# gydrodrive_discreteControl.net
KiCad netlist of a schematic drawn in Altium Designer
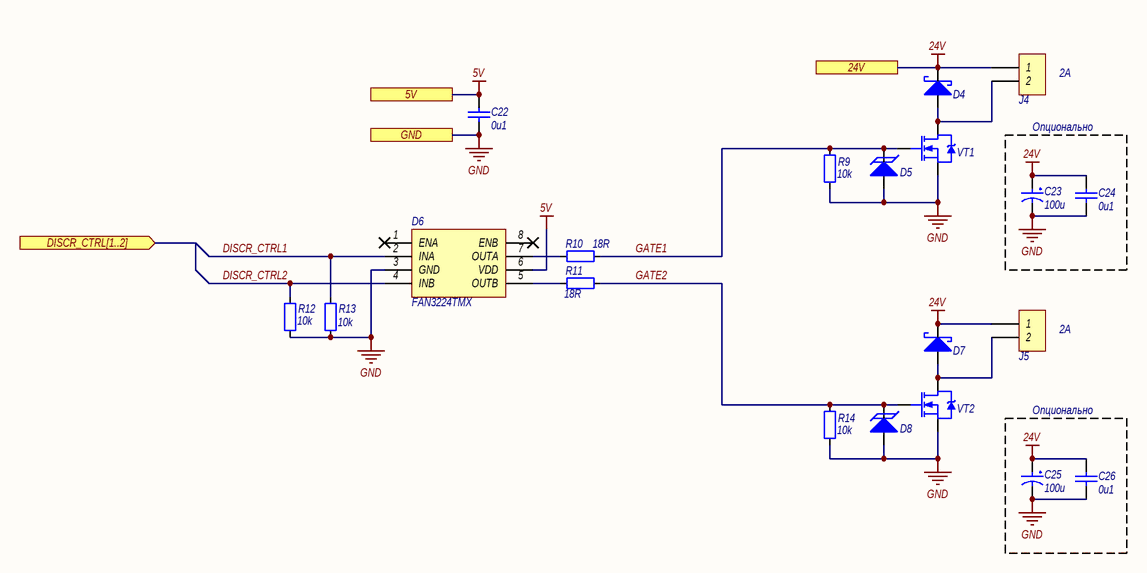
[diagram p0: gydrodrive_discreteControl.SchDoc]

(export (version "E")
  (design (tool "Eeschema 10.0.6"))
  (components
    (comp (ref "C22")
      (value "CAP_0805")
      (footprint "CAPC2012-0805M")
      (description "Конденсатор керамический, корпус 0805")
      (fields
        (field (name "CAPACITANCE") "0u1")
        (field (name "PART NUMBER") "CAPC_0805")
        (field (name "VOLTAGE") "50V")
      )
      (libsource (lib "StdLib") (part "CAP"))
    )
    (comp (ref "C23")
      (value "TKR101M1HF11")
      (footprint "ECAP811.5")
      (description "Конденсатор электролитический")
      (fields (field (name "CAPACITANCE") "100u") (field (name "VOLTAGE") "50V"))
      (libsource (lib "StdLib") (part "CAP_POL"))
    )
    (comp (ref "C24")
      (value "CAP_1206")
      (footprint "CAPC3216-1206M")
      (description "Конденсатор керамический, корпус 1206")
      (fields
        (field (name "CAPACITANCE") "0u1")
        (field (name "PART NUMBER") "CAPC_1206")
        (field (name "VOLTAGE") "50V")
      )
      (libsource (lib "StdLib") (part "CAP"))
    )
    (comp (ref "C25")
      (value "TKR101M1HF11")
      (footprint "ECAP811.5")
      (description "Конденсатор электролитический")
      (fields (field (name "CAPACITANCE") "100u") (field (name "VOLTAGE") "50V"))
      (libsource (lib "StdLib") (part "CAP_POL"))
    )
    (comp (ref "C26")
      (value "CAP_1206")
      (footprint "CAPC3216-1206M")
      (description "Конденсатор керамический, корпус 1206")
      (fields
        (field (name "CAPACITANCE") "0u1")
        (field (name "PART NUMBER") "CAPC_1206")
        (field (name "VOLTAGE") "50V")
      )
      (libsource (lib "StdLib") (part "CAP"))
    )
    (comp (ref "D4")
      (value "SS24")
      (footprint "SMB_M")
      (description "Диод Шоттки")
      (fields (field (name "VOLTAGE") "40V"))
      (libsource (lib "StdLib") (part "SCHOTTKY"))
    )
    (comp (ref "D5")
      (value "SMAJ12A")
      (footprint "SMA_M")
      (description "Защитный диод (TVS)")
      (fields (field (name "VOLTAGE") "12V") (field (name "POWER") "400W"))
      (libsource (lib "StdLib") (part "TVS"))
    )
    (comp (ref "D6")
      (value "FAN3224TMX")
      (footprint "SO8_M")
      (description "Сдвоенный драйвер ключей нижнего уровня")
      (libsource (lib "StdLib") (part "MOSFET_DRIVER_LL_SO8"))
    )
    (comp (ref "D7")
      (value "SS24")
      (footprint "SMB_M")
      (description "Диод Шоттки")
      (fields (field (name "VOLTAGE") "40V"))
      (libsource (lib "StdLib") (part "SCHOTTKY"))
    )
    (comp (ref "D8")
      (value "SMAJ12A")
      (footprint "SMA_M")
      (description "Защитный диод (TVS)")
      (fields (field (name "VOLTAGE") "12V") (field (name "POWER") "400W"))
      (libsource (lib "StdLib") (part "TVS"))
    )
    (comp (ref "J4")
      (value "DG142V-5.08-02P")
      (footprint "DG142V-5.08-02P")
      (description "Клеммник 2-контактный, шаг 5.08 мм")
      (libsource (lib "StdLib") (part "PIN1x2"))
    )
    (comp (ref "J5")
      (value "DG142V-5.08-02P")
      (footprint "DG142V-5.08-02P")
      (description "Клеммник 2-контактный, шаг 5.08 мм")
      (libsource (lib "StdLib") (part "PIN1x2"))
    )
    (comp (ref "R9")
      (value "RES_0805")
      (footprint "RESC2012-0805M")
      (description "Рез-р, корпус 0805")
      (fields
        (field (name "RESISTANCE") "10k")
        (field (name "PART NUMBER") "RESC_0805")
        (field (name "TOLERANCE") "5%")
      )
      (libsource (lib "StdLib") (part "RES"))
    )
    (comp (ref "R10")
      (value "RES_0805")
      (footprint "RESC2012-0805M")
      (description "Рез-р, корпус 0805")
      (fields
        (field (name "RESISTANCE") "18R")
        (field (name "PART NUMBER") "RESC_0805")
        (field (name "TOLERANCE") "5%")
      )
      (libsource (lib "") (part "RES_1"))
    )
    (comp (ref "R11")
      (value "RES_0805")
      (footprint "RESC2012-0805M")
      (description "Рез-р, корпус 0805")
      (fields
        (field (name "RESISTANCE") "18R")
        (field (name "PART NUMBER") "RESC_0805")
        (field (name "TOLERANCE") "5%")
      )
      (libsource (lib "") (part "RES_1"))
    )
    (comp (ref "R12")
      (value "RES_0805")
      (footprint "RESC2012-0805M")
      (description "Рез-р, корпус 0805")
      (fields
        (field (name "RESISTANCE") "10k")
        (field (name "PART NUMBER") "RESC_0805")
        (field (name "TOLERANCE") "5%")
      )
      (libsource (lib "StdLib") (part "RES"))
    )
    (comp (ref "R13")
      (value "RES_0805")
      (footprint "RESC2012-0805M")
      (description "Рез-р, корпус 0805")
      (fields
        (field (name "RESISTANCE") "10k")
        (field (name "PART NUMBER") "RESC_0805")
        (field (name "TOLERANCE") "5%")
      )
      (libsource (lib "StdLib") (part "RES"))
    )
    (comp (ref "R14")
      (value "RES_0805")
      (footprint "RESC2012-0805M")
      (description "Рез-р, корпус 0805")
      (fields
        (field (name "RESISTANCE") "10k")
        (field (name "PART NUMBER") "RESC_0805")
        (field (name "TOLERANCE") "5%")
      )
      (libsource (lib "StdLib") (part "RES"))
    )
    (comp (ref "VT1")
      (value "20N06")
      (footprint "TO-252AA_M")
      (description "Полевой транзистор")
      (fields (field (name "VOLTAGE") "60V"))
      (libsource (lib "StdLib") (part "MOSFETN_TO"))
    )
    (comp (ref "VT2")
      (value "20N06")
      (footprint "TO-252AA_M")
      (description "Полевой транзистор")
      (fields (field (name "VOLTAGE") "60V"))
      (libsource (lib "StdLib") (part "MOSFETN_TO"))
    )
  )
  (nets
    (net (code "1") (name "/DISCR_CTRL1") (class "Default")
      (node (ref "D6") (pin "2") (pinfunction "INA_2") (pintype "passive"))
      (node (ref "R13") (pin "2") (pinfunction "2_2") (pintype "passive"))
    )
    (net (code "2") (name "/DISCR_CTRL2") (class "Default")
      (node (ref "D6") (pin "4") (pinfunction "INB_4") (pintype "passive"))
      (node (ref "R12") (pin "2") (pinfunction "2_2") (pintype "passive"))
    )
    (net (code "4") (name "/GATE1") (class "Default")
      (node (ref "D5") (pin "1") (pinfunction "K_1") (pintype "passive"))
      (node (ref "R10") (pin "1") (pinfunction "1_1") (pintype "passive"))
      (node (ref "R9") (pin "2") (pinfunction "2_2") (pintype "passive"))
      (node (ref "VT1") (pin "1") (pinfunction "G_1") (pintype "passive"))
    )
    (net (code "5") (name "/GATE2") (class "Default")
      (node (ref "D8") (pin "1") (pinfunction "K_1") (pintype "passive"))
      (node (ref "R11") (pin "1") (pinfunction "1_1") (pintype "passive"))
      (node (ref "R14") (pin "2") (pinfunction "2_2") (pintype "passive"))
      (node (ref "VT2") (pin "1") (pinfunction "G_1") (pintype "passive"))
    )
    (net (code "6") (name "5V") (class "Default")
      (node (ref "C22") (pin "2") (pinfunction "2_2") (pintype "passive"))
      (node (ref "D6") (pin "6") (pinfunction "VDD_6") (pintype "passive"))
    )
    (net (code "7") (name "24V") (class "Default")
      (node (ref "C23") (pin "1") (pinfunction "1_1") (pintype "passive"))
      (node (ref "C24") (pin "2") (pinfunction "2_2") (pintype "passive"))
      (node (ref "C25") (pin "1") (pinfunction "1_1") (pintype "passive"))
      (node (ref "C26") (pin "2") (pinfunction "2_2") (pintype "passive"))
      (node (ref "D4") (pin "1") (pinfunction "K_1") (pintype "passive"))
      (node (ref "D7") (pin "1") (pinfunction "K_1") (pintype "passive"))
      (node (ref "J4") (pin "1") (pinfunction "1_1") (pintype "passive"))
      (node (ref "J5") (pin "1") (pinfunction "1_1") (pintype "passive"))
    )
    (net (code "8") (name "GND") (class "Default")
      (node (ref "C22") (pin "1") (pinfunction "1_1") (pintype "passive"))
      (node (ref "C23") (pin "2") (pinfunction "2_2") (pintype "passive"))
      (node (ref "C24") (pin "1") (pinfunction "1_1") (pintype "passive"))
      (node (ref "C25") (pin "2") (pinfunction "2_2") (pintype "passive"))
      (node (ref "C26") (pin "1") (pinfunction "1_1") (pintype "passive"))
      (node (ref "D5") (pin "2") (pinfunction "A_2") (pintype "passive"))
      (node (ref "D6") (pin "3") (pinfunction "GND_3") (pintype "passive"))
      (node (ref "D8") (pin "2") (pinfunction "A_2") (pintype "passive"))
      (node (ref "R12") (pin "1") (pinfunction "1_1") (pintype "passive"))
      (node (ref "R13") (pin "1") (pinfunction "1_1") (pintype "passive"))
      (node (ref "R14") (pin "1") (pinfunction "1_1") (pintype "passive"))
      (node (ref "R9") (pin "1") (pinfunction "1_1") (pintype "passive"))
      (node (ref "VT1") (pin "3") (pinfunction "S_3") (pintype "passive"))
      (node (ref "VT2") (pin "3") (pinfunction "S_3") (pintype "passive"))
    )
    (net (code "9") (name "Net-(D4-A)") (class "Default")
      (node (ref "D4") (pin "2") (pinfunction "A_2") (pintype "passive"))
      (node (ref "J4") (pin "2") (pinfunction "2_2") (pintype "passive"))
      (node (ref "VT1") (pin "2") (pinfunction "D_2") (pintype "passive"))
    )
    (net (code "10") (name "Net-(D6-OUTA)") (class "Default")
      (node (ref "D6") (pin "7") (pinfunction "OUTA_7") (pintype "passive"))
      (node (ref "R10") (pin "2") (pinfunction "2_2") (pintype "passive"))
    )
    (net (code "11") (name "Net-(D6-OUTB)") (class "Default")
      (node (ref "D6") (pin "5") (pinfunction "OUTB_5") (pintype "passive"))
      (node (ref "R11") (pin "2") (pinfunction "2_2") (pintype "passive"))
    )
    (net (code "12") (name "Net-(D7-A)") (class "Default")
      (node (ref "D7") (pin "2") (pinfunction "A_2") (pintype "passive"))
      (node (ref "J5") (pin "2") (pinfunction "2_2") (pintype "passive"))
      (node (ref "VT2") (pin "2") (pinfunction "D_2") (pintype "passive"))
    )
    (net (code "13") (name "unconnected-(D6-ENA-Pad1)") (class "Default")
      (node (ref "D6") (pin "1") (pinfunction "ENA_1") (pintype "passive+no_connect"))
    )
    (net (code "14") (name "unconnected-(D6-ENB-Pad8)") (class "Default")
      (node (ref "D6") (pin "8") (pinfunction "ENB_8") (pintype "passive+no_connect"))
    )
  )
)
